# -_-__20241004.net
KiCad netlist of a schematic drawn in Altium Designer
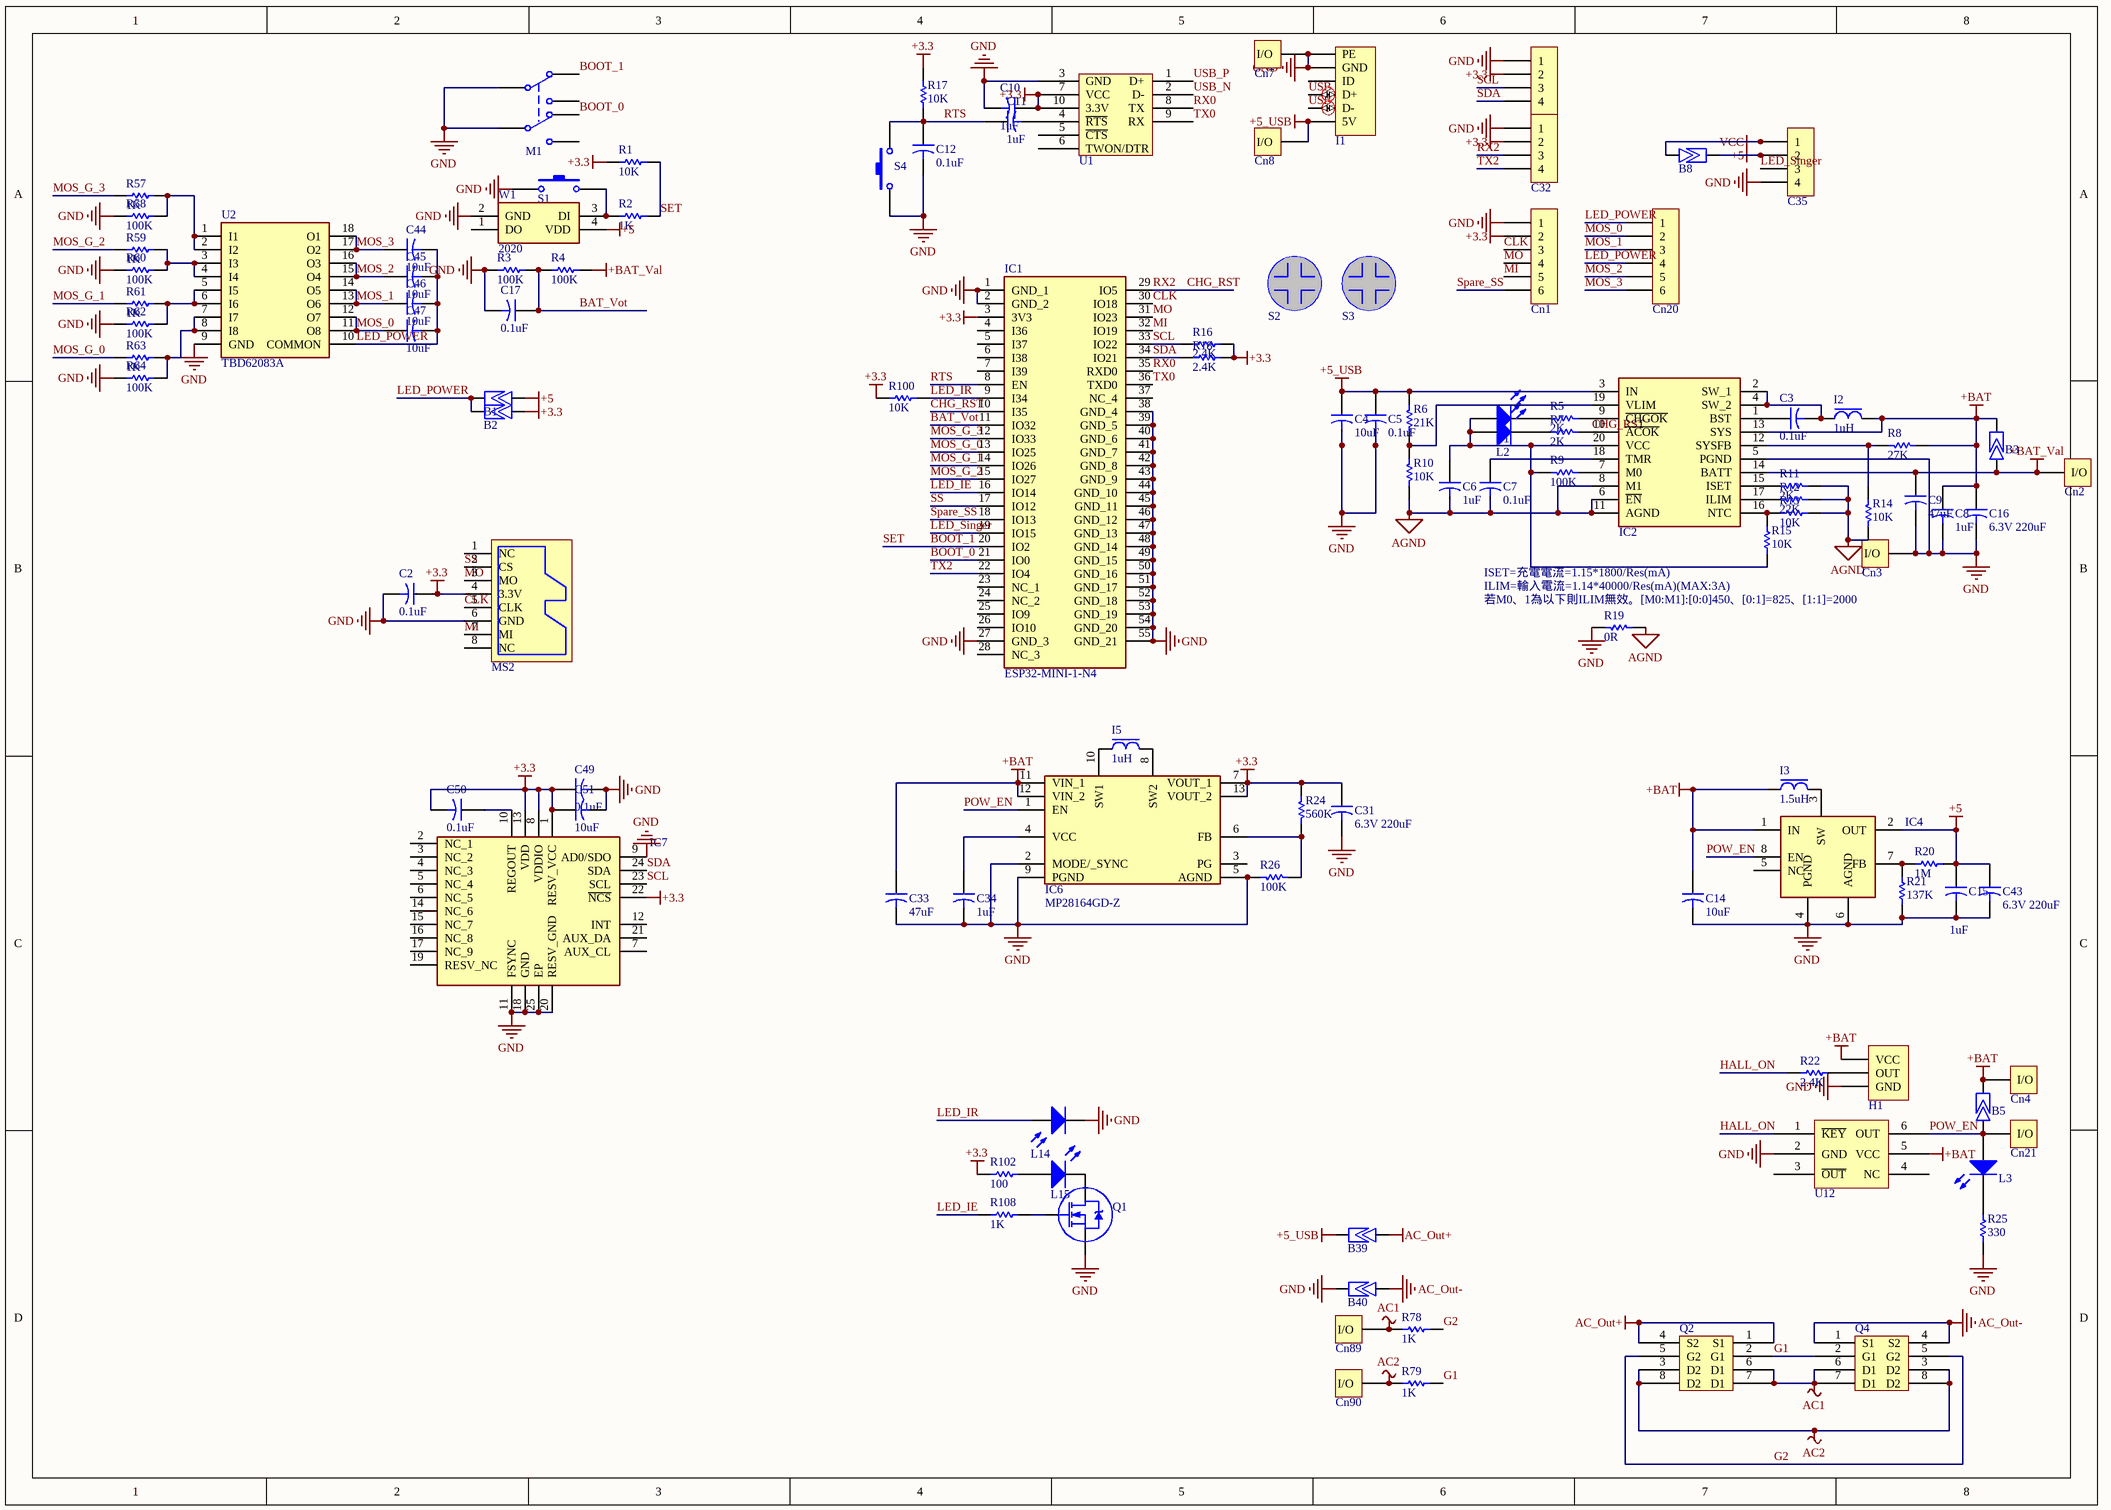
[diagram p0: 幻影光靈-學院-武器_20241004.SchDoc]

(export (version "E")
  (design (tool "Eeschema 10.0.6"))
  (components
    (comp (ref "B1")
      (value "不短路")
      (footprint "BYPASS-0805")
      (description "短路焊點(如標註短路則需額外補錫使其短路)")
      (libsource (lib "MyLibray") (part "Bypass"))
    )
    (comp (ref "B2")
      (value "短路")
      (footprint "BYPASS-0805")
      (description "短路焊點(如標註短路則需額外補錫使其短路)")
      (libsource (lib "MyLibray") (part "Bypass"))
    )
    (comp (ref "B3")
      (value "不短路")
      (footprint "BYPASS-0805")
      (description "短路焊點(如標註短路則需額外補錫使其短路)")
      (libsource (lib "MyLibray") (part "Bypass"))
    )
    (comp (ref "B5")
      (value "短路")
      (footprint "BYPASS-0402")
      (description "短路焊點(如標註短路則需額外補錫使其短路)")
      (libsource (lib "MyLibray") (part "Bypass"))
    )
    (comp (ref "B8")
      (value "短路")
      (footprint "BYPASS-0805")
      (description "短路焊點(如標註短路則需額外補錫使其短路)")
      (libsource (lib "MyLibray") (part "Bypass"))
    )
    (comp (ref "B39")
      (value "短路")
      (footprint "BYPASS-1206")
      (description "短路焊點(如標註短路則需額外補錫使其短路)")
      (libsource (lib "MyLibray") (part "Bypass"))
    )
    (comp (ref "B40")
      (value "短路")
      (footprint "BYPASS-1206")
      (description "短路焊點(如標註短路則需額外補錫使其短路)")
      (libsource (lib "MyLibray") (part "Bypass"))
    )
    (comp (ref "C1")
      (value "KF2510-4")
      (footprint "Connector_KF2510-4A")
      (description "接線端子")
      (libsource (lib "MyLibray") (part "Contact(4P)"))
    )
    (comp (ref "C2")
      (value "0.1uF")
      (footprint "Cap-0603")
      (description "電容")
      (libsource (lib "MyLibray") (part "Cap"))
    )
    (comp (ref "C3")
      (value "0.1uF")
      (footprint "Cap-0603")
      (description "電容")
      (libsource (lib "MyLibray") (part "Cap"))
    )
    (comp (ref "C4")
      (value "10uF")
      (footprint "Cap-0603")
      (description "電容")
      (libsource (lib "MyLibray") (part "Cap"))
    )
    (comp (ref "C5")
      (value "0.1uF")
      (footprint "Cap-0603")
      (description "電容")
      (libsource (lib "MyLibray") (part "Cap"))
    )
    (comp (ref "C6")
      (value "1uF")
      (footprint "Cap-0603")
      (description "電容")
      (libsource (lib "MyLibray") (part "Cap"))
    )
    (comp (ref "C7")
      (value "0.1uF")
      (footprint "Cap-0603")
      (description "電容")
      (libsource (lib "MyLibray") (part "Cap"))
    )
    (comp (ref "C8")
      (value "1uF")
      (footprint "Cap-0603")
      (description "電容")
      (libsource (lib "MyLibray") (part "Cap"))
    )
    (comp (ref "C9")
      (value "47uF")
      (footprint "CAP-1210")
      (description "電容")
      (libsource (lib "MyLibray") (part "Cap"))
    )
    (comp (ref "C10")
      (value "1uF")
      (footprint "Cap-0603")
      (description "電容")
      (libsource (lib "MyLibray") (part "Cap"))
    )
    (comp (ref "C11")
      (value "1uF")
      (footprint "Cap-0603")
      (description "電容")
      (libsource (lib "") (part "Cap_1"))
    )
    (comp (ref "C12")
      (value "0.1uF")
      (footprint "Cap-0603")
      (description "電容")
      (libsource (lib "") (part "Cap_1"))
    )
    (comp (ref "C14")
      (value "10uF")
      (footprint "Cap-0603")
      (description "電容")
      (libsource (lib "MyLibray") (part "Cap"))
    )
    (comp (ref "C15")
      (value "1uF")
      (footprint "Cap-0603")
      (description "電容")
      (libsource (lib "MyLibray") (part "Cap"))
    )
    (comp (ref "C16")
      (value "6.3V 220uF")
      (footprint "CAP-B3528")
      (description "電容")
      (libsource (lib "MyLibray") (part "Cap"))
    )
    (comp (ref "C17")
      (value "0.1uF")
      (footprint "Cap-0603")
      (description "電容")
      (libsource (lib "MyLibray") (part "Cap"))
    )
    (comp (ref "C31")
      (value "6.3V 220uF")
      (footprint "CAP-B3528")
      (description "電容")
      (libsource (lib "MyLibray") (part "Cap"))
    )
    (comp (ref "C32")
      (value "KF2510-4")
      (footprint "Connector_KF2510-4A")
      (description "接線端子")
      (libsource (lib "MyLibray") (part "Contact(4P)"))
    )
    (comp (ref "C33")
      (value "47uF")
      (footprint "Cap-0603")
      (description "電容")
      (libsource (lib "MyLibray") (part "Cap"))
    )
    (comp (ref "C34")
      (value "1uF")
      (footprint "Cap-0603")
      (description "電容")
      (libsource (lib "MyLibray") (part "Cap"))
    )
    (comp (ref "C35")
      (value "KF2510-4")
      (footprint "Connector_KF2510-4A")
      (description "接線端子")
      (libsource (lib "MyLibray") (part "Contact(4P)"))
    )
    (comp (ref "C43")
      (value "6.3V 220uF")
      (footprint "CAP-B3528")
      (description "電容")
      (libsource (lib "MyLibray") (part "Cap"))
    )
    (comp (ref "C44")
      (value "10uF")
      (footprint "Cap-0603")
      (description "電容")
      (libsource (lib "MyLibray") (part "Cap"))
    )
    (comp (ref "C45")
      (value "10uF")
      (footprint "Cap-0603")
      (description "電容")
      (libsource (lib "MyLibray") (part "Cap"))
    )
    (comp (ref "C46")
      (value "10uF")
      (footprint "Cap-0603")
      (description "電容")
      (libsource (lib "MyLibray") (part "Cap"))
    )
    (comp (ref "C47")
      (value "10uF")
      (footprint "Cap-0603")
      (description "電容")
      (libsource (lib "MyLibray") (part "Cap"))
    )
    (comp (ref "C49")
      (value "0.1uF")
      (footprint "Cap-0603")
      (description "電容")
      (libsource (lib "MyLibray") (part "Cap"))
    )
    (comp (ref "C50")
      (value "0.1uF")
      (footprint "Cap-0603")
      (description "電容")
      (libsource (lib "MyLibray") (part "Cap"))
    )
    (comp (ref "C51")
      (value "10uF")
      (footprint "Cap-0603")
      (description "電容")
      (libsource (lib "MyLibray") (part "Cap"))
    )
    (comp (ref "Cn1")
      (value "KF2510-6")
      (footprint "Connector_KF2510-6A")
      (description "接線端子")
      (libsource (lib "MyLibray") (part "Contact(6P)"))
    )
    (comp (ref "Cn2")
      (value "Contact")
      (footprint "Contact_Joints1*0.5")
      (description "接線端子、接點、郵票孔(非焊接元件)")
      (libsource (lib "") (part "Contact_2"))
    )
    (comp (ref "Cn3")
      (value "Contact")
      (footprint "Contact_Joints1*0.5")
      (description "接線端子、接點、郵票孔(非焊接元件)")
      (libsource (lib "") (part "Contact_1"))
    )
    (comp (ref "Cn4")
      (value "Contact")
      (footprint "Contact_Joints1*0.5")
      (description "接線端子、接點、郵票孔(非焊接元件)")
      (libsource (lib "") (part "Contact_2"))
    )
    (comp (ref "Cn7")
      (value "Contact")
      (footprint "Contact_Joints1*0.5")
      (description "接線端子、接點、郵票孔(非焊接元件)")
      (libsource (lib "") (part "Contact_1"))
    )
    (comp (ref "Cn8")
      (value "Contact")
      (footprint "Contact_Joints1*0.5")
      (description "接線端子、接點、郵票孔(非焊接元件)")
      (libsource (lib "") (part "Contact_1"))
    )
    (comp (ref "Cn20")
      (value "KF2510-6")
      (footprint "Connector_KF2510-6A")
      (description "接線端子")
      (libsource (lib "MyLibray") (part "Contact(6P)"))
    )
    (comp (ref "Cn21")
      (value "Contact")
      (footprint "Contact_Joints1*0.5")
      (description "接線端子、接點、郵票孔(非焊接元件)")
      (libsource (lib "") (part "Contact_2"))
    )
    (comp (ref "Cn89")
      (value "Contact")
      (footprint "Contact_Joints1*0.5")
      (description "接線端子、接點、郵票孔(非焊接元件)")
      (libsource (lib "MyLibray") (part "Contact"))
    )
    (comp (ref "Cn90")
      (value "Contact")
      (footprint "Contact_Joints1*0.5")
      (description "接線端子、接點、郵票孔(非焊接元件)")
      (libsource (lib "MyLibray") (part "Contact"))
    )
    (comp (ref "H1")
      (value "A3212#不用SMT")
      (footprint "SOT 23-3")
      (description "感測器_霍爾")
      (libsource (lib "MyLibray") (part "Sensor_Hall"))
    )
    (comp (ref "I1")
      (value "Interface_USB-Micro")
      (footprint "Interface_USB-micro")
      (description "接頭_USB-Micro")
      (libsource (lib "MyLibray") (part "Interface_USB-Micro"))
    )
    (comp (ref "I2")
      (value "1uH")
      (footprint "Inductor-0630")
      (description "電感")
      (libsource (lib "MyLibray") (part "Inductor"))
    )
    (comp (ref "I3")
      (value "1.5uH")
      (footprint "Inductor-0630")
      (description "電感")
      (libsource (lib "MyLibray") (part "Inductor"))
    )
    (comp (ref "I5")
      (value "1uH")
      (footprint "Inductor-0630")
      (description "一體成型電感")
      (libsource (lib "") (part "Inductor_1"))
    )
    (comp (ref "IC1")
      (value "ESP32-MINI-1-N4")
      (footprint "SamacSys:ESP32MINI1N4")
      (description "Integrated Circuit")
      (fields (field (name "MOUSER PART NUMBER") "356-ESP32-MINI1PH3Q0"))
      (libsource (lib "*") (part "ESP32-MINI-1-N4"))
    )
    (comp (ref "IC2")
      (value "MP2617BGL-P")
      (footprint "MP2617BGL")
      (fields (field (name "MOUSER PART NUMBER") "946-MP2617BGL-P"))
      (libsource (lib "MyLibray") (part "MP2617BGL-P"))
    )
    (comp (ref "IC4")
      (value "MP3414AGJ-Z")
      (footprint "SOT 23-8")
      (description "同步升压IC")
      (fields
        (field (name "MANUFACTURER_PART_NUMBER") "MP3414DJ-LF-Z")
        (field (name "MOUSER PART NUMBER") "946-MP3414DJLFZ")
      )
      (libsource (lib "MyLibray") (part "MP3414DJ-LF-Z"))
    )
    (comp (ref "IC6")
      (value "MP28164GD-Z")
      (footprint "MP28164GDZ")
      (description "升降壓IC 2.5~5.5 to 1.5~5")
      (fields (field (name "MOUSER PART NUMBER") "946-MP28164GD-Z"))
      (libsource (lib "MyLibray") (part "MP28164GD-Z"))
    )
    (comp (ref "IC7")
      (value "MPU-9250")
      (footprint "QFN-24")
      (description "I2C,SPI,9軸陀螺儀")
      (fields (field (name "MOUSER PART NUMBER") "410-MPU-9250"))
      (libsource (lib "MyLibray") (part "MPU-9250"))
    )
    (comp (ref "L1")
      (value "紅")
      (footprint "LED-0603")
      (description "LED")
      (libsource (lib "MyLibray") (part "LED"))
    )
    (comp (ref "L2")
      (value "綠")
      (footprint "LED-0603")
      (description "LED")
      (libsource (lib "MyLibray") (part "LED"))
    )
    (comp (ref "L3")
      (value "綠")
      (footprint "LED-0603")
      (description "LED")
      (libsource (lib "MyLibray") (part "LED"))
    )
    (comp (ref "L14")
      (value "LED-IR")
      (footprint "LED-IR-1206")
      (description "LED,紅外線接收")
      (libsource (lib "MyLibray") (part "LED-IR"))
    )
    (comp (ref "L15")
      (value "LED-IE")
      (footprint "LED-IE-1206")
      (description "LED,,紅外線發射")
      (libsource (lib "") (part "LED_1"))
    )
    (comp (ref "M1")
      (value "MST22D18G2")
      (footprint "Switch_MST22D18G2")
      (description "開關_滑動_2通道")
      (libsource (lib "MyLibray") (part "Switch_Slide_2"))
    )
    (comp (ref "MS2")
      (value "Interface_MicroSD card slot")
      (footprint "Interface_MicroSD card slot")
      (description "Micro SD 卡座")
      (libsource (lib "MyLibray") (part "Interface_MicroSD card slot"))
    )
    (comp (ref "Q1")
      (value "AO3400")
      (footprint "SOT 23-3")
      (description "場效電晶體_N")
      (libsource (lib "MyLibray") (part "MOS-N"))
    )
    (comp (ref "Q2")
      (value "MOS_Dual P_AON2801")
      (footprint "DFN-6_2x2")
      (description "MOS,雙PMOS")
      (libsource (lib "MyLibray") (part "MOS_Dual P_AON2801"))
    )
    (comp (ref "Q4")
      (value "MOS_Dual N_AON2800")
      (footprint "DFN-6_2x2")
      (description "MOS,雙NMOS")
      (libsource (lib "MyLibray") (part "MOS_Dual N_AON2800"))
    )
    (comp (ref "R1")
      (value "10K")
      (footprint "Res-0603")
      (description "電阻")
      (libsource (lib "MyLibray") (part "Res"))
    )
    (comp (ref "R2")
      (value "1K")
      (footprint "Res-0603")
      (description "電阻")
      (libsource (lib "MyLibray") (part "Res"))
    )
    (comp (ref "R3")
      (value "100K")
      (footprint "Res-0603")
      (description "電阻")
      (libsource (lib "MyLibray") (part "Res"))
    )
    (comp (ref "R4")
      (value "100K")
      (footprint "Res-0603")
      (description "電阻")
      (libsource (lib "MyLibray") (part "Res"))
    )
    (comp (ref "R5")
      (value "2K")
      (footprint "Res-0603")
      (description "電阻")
      (libsource (lib "MyLibray") (part "Res"))
    )
    (comp (ref "R6")
      (value "21K")
      (footprint "Res-0603")
      (description "電阻")
      (libsource (lib "MyLibray") (part "Res"))
    )
    (comp (ref "R7")
      (value "2K")
      (footprint "Res-0603")
      (description "電阻")
      (libsource (lib "MyLibray") (part "Res"))
    )
    (comp (ref "R8")
      (value "27K")
      (footprint "Res-0603")
      (description "電阻")
      (libsource (lib "MyLibray") (part "Res"))
    )
    (comp (ref "R9")
      (value "100K")
      (footprint "Res-0603")
      (description "電阻")
      (libsource (lib "MyLibray") (part "Res"))
    )
    (comp (ref "R10")
      (value "10K")
      (footprint "Res-0603")
      (description "電阻")
      (libsource (lib "MyLibray") (part "Res"))
    )
    (comp (ref "R11")
      (value "2K")
      (footprint "Res-0603")
      (description "電阻")
      (libsource (lib "MyLibray") (part "Res"))
    )
    (comp (ref "R12")
      (value "22K")
      (footprint "Res-0603")
      (description "電阻")
      (libsource (lib "MyLibray") (part "Res"))
    )
    (comp (ref "R13")
      (value "10K")
      (footprint "Res-0603")
      (description "電阻")
      (libsource (lib "MyLibray") (part "Res"))
    )
    (comp (ref "R14")
      (value "10K")
      (footprint "Res-0603")
      (description "電阻")
      (libsource (lib "MyLibray") (part "Res"))
    )
    (comp (ref "R15")
      (value "10K")
      (footprint "Res-0603")
      (description "電阻")
      (libsource (lib "MyLibray") (part "Res"))
    )
    (comp (ref "R16")
      (value "2.4K")
      (footprint "Res-0603")
      (description "電阻")
      (libsource (lib "MyLibray") (part "Res"))
    )
    (comp (ref "R17")
      (value "10K")
      (footprint "Res-0603")
      (description "電阻")
      (libsource (lib "MyLibray") (part "Res"))
    )
    (comp (ref "R18")
      (value "2.4K")
      (footprint "Res-0603")
      (description "電阻")
      (libsource (lib "MyLibray") (part "Res"))
    )
    (comp (ref "R19")
      (value "0R")
      (footprint "Res-0603")
      (description "電阻")
      (libsource (lib "MyLibray") (part "Res"))
    )
    (comp (ref "R20")
      (value "1M")
      (footprint "Res-0603")
      (description "電阻")
      (libsource (lib "MyLibray") (part "Res"))
    )
    (comp (ref "R21")
      (value "137K")
      (footprint "Res-0603")
      (description "電阻")
      (libsource (lib "MyLibray") (part "Res"))
    )
    (comp (ref "R22")
      (value "2.4K")
      (footprint "Res-0603")
      (description "電阻")
      (libsource (lib "MyLibray") (part "Res"))
    )
    (comp (ref "R24")
      (value "560K")
      (footprint "Res-0603")
      (description "電阻")
      (libsource (lib "MyLibray") (part "Res"))
    )
    (comp (ref "R25")
      (value "330")
      (footprint "Res-0603")
      (description "電阻")
      (libsource (lib "MyLibray") (part "Res"))
    )
    (comp (ref "R26")
      (value "100K")
      (footprint "Res-0603")
      (description "電阻")
      (libsource (lib "MyLibray") (part "Res"))
    )
    (comp (ref "R57")
      (value "1K")
      (footprint "Res-0603")
      (description "電阻")
      (libsource (lib "MyLibray") (part "Res"))
    )
    (comp (ref "R58")
      (value "100K")
      (footprint "Res-0603")
      (description "電阻")
      (libsource (lib "MyLibray") (part "Res"))
    )
    (comp (ref "R59")
      (value "1K")
      (footprint "Res-0603")
      (description "電阻")
      (libsource (lib "MyLibray") (part "Res"))
    )
    (comp (ref "R60")
      (value "100K")
      (footprint "Res-0603")
      (description "電阻")
      (libsource (lib "MyLibray") (part "Res"))
    )
    (comp (ref "R61")
      (value "1K")
      (footprint "Res-0603")
      (description "電阻")
      (libsource (lib "MyLibray") (part "Res"))
    )
    (comp (ref "R62")
      (value "100K")
      (footprint "Res-0603")
      (description "電阻")
      (libsource (lib "MyLibray") (part "Res"))
    )
    (comp (ref "R63")
      (value "1K")
      (footprint "Res-0603")
      (description "電阻")
      (libsource (lib "MyLibray") (part "Res"))
    )
    (comp (ref "R64")
      (value "100K")
      (footprint "Res-0603")
      (description "電阻")
      (libsource (lib "MyLibray") (part "Res"))
    )
    (comp (ref "R78")
      (value "1K")
      (footprint "Res-0603")
      (description "電阻")
      (libsource (lib "MyLibray") (part "Res"))
    )
    (comp (ref "R79")
      (value "1K")
      (footprint "Res-0603")
      (description "電阻")
      (libsource (lib "MyLibray") (part "Res"))
    )
    (comp (ref "R100")
      (value "10K")
      (footprint "Res-0603")
      (description "電阻")
      (libsource (lib "MyLibray") (part "Res"))
    )
    (comp (ref "R102")
      (value "100")
      (footprint "Res-0603")
      (description "電阻")
      (libsource (lib "MyLibray") (part "Res"))
    )
    (comp (ref "R108")
      (value "1K")
      (footprint "Res-0603")
      (description "電阻")
      (libsource (lib "MyLibray") (part "Res"))
    )
    (comp (ref "S1")
      (value "Switch")
      (footprint "Switch SMD-3.6*6*2.5")
      (description "開關_按鍵")
      (libsource (lib "MyLibray") (part "Switch"))
    )
    (comp (ref "S2")
      (value "M3")
      (footprint "Screw M3")
      (description "螺絲(非焊接元件)")
      (libsource (lib "MyLibray") (part "Screw"))
    )
    (comp (ref "S3")
      (value "M3")
      (footprint "Screw M3")
      (description "螺絲(非焊接元件)")
      (libsource (lib "MyLibray") (part "Screw"))
    )
    (comp (ref "S4")
      (value "Switch")
      (footprint "Switch SMD-3.6*6*2.5")
      (description "開關_按鍵")
      (libsource (lib "MyLibray") (part "Switch"))
    )
    (comp (ref "U1")
      (value "CH340X")
      (footprint "SSOP-10")
      (description "USB轉TTL芯片")
      (libsource (lib "MyLibray") (part "CH340X"))
    )
    (comp (ref "U2")
      (value "TBD62083A")
      (footprint "TSSOP-18")
      (description "閘極驅動器 P型 50V 0.5A")
      (fields
        (field (name "MOUSER PART NUMBER") "757-TBD60183AFNGEL")
        (field (name "MANUFACTURER_PART_NUMBER") "TBD62083AFNG,EL")
      )
      (libsource (lib "MyLibray") (part "TBD62083A"))
    )
    (comp (ref "U12")
      (value "CS2130#不用SMT")
      (footprint "SOT 23-6")
      (description "單鍵ON/OFF芯片")
      (libsource (lib "MyLibray") (part "CS2130"))
    )
    (comp (ref "W1")
      (value "2020")
      (footprint "LED-WS2812B-2020")
      (description "LED幻彩燈珠")
      (fields (field (name "MANUFACTURER_PART_NUMBER") "4684") (field (name "MOUSER PART NUMBER") "485-4684"))
      (libsource (lib "MyLibray") (part "WS2812B"))
    )
  )
  (nets
    (net (code "1") (name "+3.3") (class "Default")
      (node (ref "B2") (pin "2") (pinfunction "2_2") (pintype "passive"))
      (node (ref "C1") (pin "2") (pinfunction "2_2") (pintype "passive"))
      (node (ref "C10") (pin "1") (pinfunction "1_1") (pintype "passive"))
      (node (ref "C2") (pin "1") (pinfunction "1_1") (pintype "passive"))
      (node (ref "C31") (pin "1") (pinfunction "1_1") (pintype "passive"))
      (node (ref "C32") (pin "2") (pinfunction "2_2") (pintype "passive"))
      (node (ref "C49") (pin "1") (pinfunction "1_1") (pintype "passive"))
      (node (ref "C50") (pin "2") (pinfunction "2_2") (pintype "passive"))
      (node (ref "C51") (pin "1") (pinfunction "1_1") (pintype "passive"))
      (node (ref "Cn1") (pin "2") (pinfunction "2_2") (pintype "passive"))
      (node (ref "IC1") (pin "3") (pinfunction "3V3_3") (pintype "passive"))
      (node (ref "IC6") (pin "13") (pinfunction "VOUT_2_13") (pintype "passive"))
      (node (ref "IC6") (pin "7") (pinfunction "VOUT_1_7") (pintype "passive"))
      (node (ref "IC7") (pin "1") (pinfunction "RESV_VCC_1") (pintype "passive"))
      (node (ref "IC7") (pin "13") (pinfunction "VDD_13") (pintype "passive"))
      (node (ref "IC7") (pin "22") (pinfunction "~{NCS}_22") (pintype "passive"))
      (node (ref "IC7") (pin "8") (pinfunction "VDDIO_8") (pintype "passive"))
      (node (ref "MS2") (pin "4") (pinfunction "3.3V_4") (pintype "power_in"))
      (node (ref "R1") (pin "1") (pinfunction "1_1") (pintype "passive"))
      (node (ref "R100") (pin "1") (pinfunction "1_1") (pintype "passive"))
      (node (ref "R102") (pin "1") (pinfunction "1_1") (pintype "passive"))
      (node (ref "R16") (pin "1") (pinfunction "1_1") (pintype "passive"))
      (node (ref "R17") (pin "1") (pinfunction "1_1") (pintype "passive"))
      (node (ref "R18") (pin "2") (pinfunction "2_2") (pintype "passive"))
      (node (ref "R24") (pin "2") (pinfunction "2_2") (pintype "passive"))
      (node (ref "U1") (pin "10") (pinfunction "3.3V_10") (pintype "passive"))
      (node (ref "U1") (pin "7") (pinfunction "VCC_7") (pintype "passive"))
    )
    (net (code "2") (name "+5") (class "Default")
      (node (ref "B1") (pin "2") (pinfunction "2_2") (pintype "passive"))
      (node (ref "B8") (pin "1") (pinfunction "1_1") (pintype "passive"))
      (node (ref "C15") (pin "1") (pinfunction "1_1") (pintype "passive"))
      (node (ref "C35") (pin "2") (pinfunction "2_2") (pintype "passive"))
      (node (ref "C43") (pin "1") (pinfunction "1_1") (pintype "passive"))
      (node (ref "IC4") (pin "2") (pinfunction "OUT_2") (pintype "passive"))
      (node (ref "R20") (pin "1") (pinfunction "1_1") (pintype "passive"))
      (node (ref "W1") (pin "4") (pinfunction "VDD_4") (pintype "passive"))
    )
    (net (code "3") (name "+5_USB") (class "Default")
      (node (ref "B39") (pin "1") (pinfunction "1_1") (pintype "passive"))
      (node (ref "C4") (pin "1") (pinfunction "1_1") (pintype "passive"))
      (node (ref "C5") (pin "1") (pinfunction "1_1") (pintype "passive"))
      (node (ref "Cn8") (pin "1") (pinfunction "I/O_1") (pintype "passive"))
      (node (ref "I1") (pin "1") (pinfunction "5V_1") (pintype "passive"))
      (node (ref "IC2") (pin "3") (pinfunction "IN_3") (pintype "passive"))
      (node (ref "R6") (pin "1") (pinfunction "1_1") (pintype "passive"))
    )
    (net (code "4") (name "+BAT") (class "Default")
      (node (ref "B3") (pin "1") (pinfunction "1_1") (pintype "passive"))
      (node (ref "B5") (pin "1") (pinfunction "1_1") (pintype "passive"))
      (node (ref "C14") (pin "1") (pinfunction "1_1") (pintype "passive"))
      (node (ref "C16") (pin "1") (pinfunction "1_1") (pintype "passive"))
      (node (ref "C33") (pin "1") (pinfunction "1_1") (pintype "passive"))
      (node (ref "C8") (pin "1") (pinfunction "1_1") (pintype "passive"))
      (node (ref "Cn4") (pin "1") (pinfunction "I/O_1") (pintype "passive"))
      (node (ref "H1") (pin "1") (pinfunction "VCC_1") (pintype "power_in"))
      (node (ref "I2") (pin "2") (pinfunction "2_2") (pintype "passive"))
      (node (ref "I3") (pin "1") (pinfunction "1_1") (pintype "passive"))
      (node (ref "IC2") (pin "13") (pinfunction "SYS_13") (pintype "passive"))
      (node (ref "IC4") (pin "1") (pinfunction "IN_1") (pintype "passive"))
      (node (ref "IC6") (pin "11") (pinfunction "VIN_1_11") (pintype "passive"))
      (node (ref "IC6") (pin "12") (pinfunction "VIN_2_12") (pintype "passive"))
      (node (ref "R8") (pin "2") (pinfunction "2_2") (pintype "passive"))
      (node (ref "U12") (pin "5") (pinfunction "VCC_5") (pintype "passive"))
    )
    (net (code "5") (name "+BAT_Val") (class "Default")
      (node (ref "B3") (pin "2") (pinfunction "2_2") (pintype "passive"))
      (node (ref "C9") (pin "1") (pinfunction "1_1") (pintype "passive"))
      (node (ref "Cn2") (pin "1") (pinfunction "I/O_1") (pintype "passive"))
      (node (ref "IC2") (pin "14") (pinfunction "BATT_14") (pintype "passive"))
      (node (ref "R4") (pin "2") (pinfunction "2_2") (pintype "passive"))
    )
    (net (code "6") (name "/BAT_Vot") (class "Default")
      (node (ref "C17") (pin "1") (pinfunction "1_1") (pintype "passive"))
      (node (ref "IC1") (pin "11") (pinfunction "IO32_11") (pintype "passive"))
      (node (ref "R3") (pin "2") (pinfunction "2_2") (pintype "passive"))
      (node (ref "R4") (pin "1") (pinfunction "1_1") (pintype "passive"))
    )
    (net (code "7") (name "/BOOT_0") (class "Default")
      (node (ref "IC1") (pin "21") (pinfunction "IO0_21") (pintype "passive"))
      (node (ref "M1") (pin "5") (pinfunction "5_5") (pintype "passive"))
    )
    (net (code "8") (name "/BOOT_1") (class "Default")
      (node (ref "IC1") (pin "20") (pinfunction "IO2_20") (pintype "passive"))
      (node (ref "M1") (pin "2") (pinfunction "2_2") (pintype "passive"))
      (node (ref "R1") (pin "2") (pinfunction "2_2") (pintype "passive"))
      (node (ref "R2") (pin "2") (pinfunction "2_2") (pintype "passive"))
    )
    (net (code "9") (name "/CHG_RST") (class "Default")
      (node (ref "C32") (pin "3") (pinfunction "3_3") (pintype "passive"))
      (node (ref "IC1") (pin "10") (pinfunction "I35_10") (pintype "passive"))
      (node (ref "IC1") (pin "29") (pinfunction "IO5_29") (pintype "passive"))
      (node (ref "IC2") (pin "10") (pinfunction "~{ACOK}_10") (pintype "passive"))
      (node (ref "R7") (pin "2") (pinfunction "2_2") (pintype "passive"))
    )
    (net (code "10") (name "/CLK") (class "Default")
      (node (ref "Cn1") (pin "3") (pinfunction "3_3") (pintype "passive"))
      (node (ref "IC1") (pin "30") (pinfunction "IO18_30") (pintype "passive"))
      (node (ref "MS2") (pin "5") (pinfunction "CLK_5") (pintype "passive"))
    )
    (net (code "11") (name "/G1") (class "Default")
      (node (ref "Q2") (pin "2") (pinfunction "G1_2") (pintype "passive"))
      (node (ref "Q4") (pin "2") (pinfunction "G1_2") (pintype "passive"))
      (node (ref "R79") (pin "1") (pinfunction "1_1") (pintype "passive"))
    )
    (net (code "12") (name "/G2") (class "Default")
      (node (ref "Q2") (pin "5") (pinfunction "G2_5") (pintype "passive"))
      (node (ref "Q4") (pin "5") (pinfunction "G2_5") (pintype "passive"))
      (node (ref "R78") (pin "1") (pinfunction "1_1") (pintype "passive"))
    )
    (net (code "13") (name "/HALL_ON") (class "Default")
      (node (ref "R22") (pin "1") (pinfunction "1_1") (pintype "passive"))
      (node (ref "U12") (pin "1") (pinfunction "~{KEY}_1") (pintype "passive"))
    )
    (net (code "14") (name "/LED_IE") (class "Default")
      (node (ref "IC1") (pin "16") (pinfunction "IO14_16") (pintype "passive"))
      (node (ref "R108") (pin "1") (pinfunction "1_1") (pintype "passive"))
    )
    (net (code "15") (name "/LED_IR") (class "Default")
      (node (ref "IC1") (pin "9") (pinfunction "I34_9") (pintype "passive"))
      (node (ref "L14") (pin "1") (pinfunction "A_1") (pintype "passive"))
      (node (ref "R100") (pin "2") (pinfunction "2_2") (pintype "passive"))
    )
    (net (code "16") (name "/LED_POWER") (class "Default")
      (node (ref "B1") (pin "1") (pinfunction "1_1") (pintype "passive"))
      (node (ref "B2") (pin "1") (pinfunction "1_1") (pintype "passive"))
      (node (ref "C44") (pin "2") (pinfunction "2_2") (pintype "passive"))
      (node (ref "C45") (pin "2") (pinfunction "2_2") (pintype "passive"))
      (node (ref "C46") (pin "2") (pinfunction "2_2") (pintype "passive"))
      (node (ref "C47") (pin "2") (pinfunction "2_2") (pintype "passive"))
      (node (ref "Cn20") (pin "1") (pinfunction "1_1") (pintype "passive"))
      (node (ref "Cn20") (pin "4") (pinfunction "4_4") (pintype "passive"))
      (node (ref "U2") (pin "10") (pinfunction "COMMON_10") (pintype "passive"))
    )
    (net (code "17") (name "/LED_Singer") (class "Default")
      (node (ref "C35") (pin "3") (pinfunction "3_3") (pintype "passive"))
      (node (ref "IC1") (pin "19") (pinfunction "IO15_19") (pintype "passive"))
    )
    (net (code "18") (name "/MI") (class "Default")
      (node (ref "Cn1") (pin "5") (pinfunction "5_5") (pintype "passive"))
      (node (ref "IC1") (pin "32") (pinfunction "IO19_32") (pintype "passive"))
      (node (ref "MS2") (pin "7") (pinfunction "MI_7") (pintype "passive"))
    )
    (net (code "19") (name "/MO") (class "Default")
      (node (ref "Cn1") (pin "4") (pinfunction "4_4") (pintype "passive"))
      (node (ref "IC1") (pin "31") (pinfunction "IO23_31") (pintype "passive"))
      (node (ref "MS2") (pin "3") (pinfunction "MO_3") (pintype "passive"))
    )
    (net (code "20") (name "/MOS_0") (class "Default")
      (node (ref "C47") (pin "1") (pinfunction "1_1") (pintype "passive"))
      (node (ref "Cn20") (pin "2") (pinfunction "2_2") (pintype "passive"))
      (node (ref "U2") (pin "11") (pinfunction "O8_11") (pintype "passive"))
      (node (ref "U2") (pin "12") (pinfunction "O7_12") (pintype "passive"))
    )
    (net (code "21") (name "/MOS_1") (class "Default")
      (node (ref "C46") (pin "1") (pinfunction "1_1") (pintype "passive"))
      (node (ref "Cn20") (pin "3") (pinfunction "3_3") (pintype "passive"))
      (node (ref "U2") (pin "13") (pinfunction "O6_13") (pintype "passive"))
      (node (ref "U2") (pin "14") (pinfunction "O5_14") (pintype "passive"))
    )
    (net (code "22") (name "/MOS_2") (class "Default")
      (node (ref "C45") (pin "1") (pinfunction "1_1") (pintype "passive"))
      (node (ref "Cn20") (pin "5") (pinfunction "5_5") (pintype "passive"))
      (node (ref "U2") (pin "15") (pinfunction "O4_15") (pintype "passive"))
      (node (ref "U2") (pin "16") (pinfunction "O3_16") (pintype "passive"))
    )
    (net (code "23") (name "/MOS_3") (class "Default")
      (node (ref "C44") (pin "1") (pinfunction "1_1") (pintype "passive"))
      (node (ref "Cn20") (pin "6") (pinfunction "6_6") (pintype "passive"))
      (node (ref "U2") (pin "17") (pinfunction "O2_17") (pintype "passive"))
      (node (ref "U2") (pin "18") (pinfunction "O1_18") (pintype "passive"))
    )
    (net (code "24") (name "/MOS_G_0") (class "Default")
      (node (ref "IC1") (pin "13") (pinfunction "IO25_13") (pintype "passive"))
      (node (ref "R63") (pin "1") (pinfunction "1_1") (pintype "passive"))
    )
    (net (code "25") (name "/MOS_G_1") (class "Default")
      (node (ref "IC1") (pin "14") (pinfunction "IO26_14") (pintype "passive"))
      (node (ref "R61") (pin "1") (pinfunction "1_1") (pintype "passive"))
    )
    (net (code "26") (name "/MOS_G_2") (class "Default")
      (node (ref "IC1") (pin "15") (pinfunction "IO27_15") (pintype "passive"))
      (node (ref "R59") (pin "1") (pinfunction "1_1") (pintype "passive"))
    )
    (net (code "27") (name "/MOS_G_3") (class "Default")
      (node (ref "IC1") (pin "12") (pinfunction "IO33_12") (pintype "passive"))
      (node (ref "R57") (pin "1") (pinfunction "1_1") (pintype "passive"))
    )
    (net (code "28") (name "/POW_EN") (class "Default")
      (node (ref "B5") (pin "2") (pinfunction "2_2") (pintype "passive"))
      (node (ref "Cn21") (pin "1") (pinfunction "I/O_1") (pintype "passive"))
      (node (ref "IC4") (pin "8") (pinfunction "EN_8") (pintype "passive"))
      (node (ref "IC6") (pin "1") (pinfunction "EN_1") (pintype "passive"))
      (node (ref "L3") (pin "2") (pinfunction "A_2") (pintype "passive"))
      (node (ref "U12") (pin "6") (pinfunction "OUT_6") (pintype "passive"))
    )
    (net (code "29") (name "/RTS") (class "Default")
      (node (ref "C11") (pin "1") (pinfunction "1_1") (pintype "passive"))
      (node (ref "C12") (pin "1") (pinfunction "1_1") (pintype "passive"))
      (node (ref "IC1") (pin "8") (pinfunction "EN_8") (pintype "passive"))
      (node (ref "R17") (pin "2") (pinfunction "2_2") (pintype "passive"))
      (node (ref "S4") (pin "1") (pinfunction "1_1") (pintype "passive"))
    )
    (net (code "30") (name "/RX0") (class "Default")
      (node (ref "IC1") (pin "35") (pinfunction "RXD0_35") (pintype "passive"))
      (node (ref "U1") (pin "8") (pinfunction "TX_8") (pintype "passive"))
    )
    (net (code "31") (name "/SCL") (class "Default")
      (node (ref "C1") (pin "3") (pinfunction "3_3") (pintype "passive"))
      (node (ref "IC1") (pin "33") (pinfunction "IO22_33") (pintype "passive"))
      (node (ref "IC7") (pin "23") (pinfunction "SCL_23") (pintype "passive"))
      (node (ref "R16") (pin "2") (pinfunction "2_2") (pintype "passive"))
    )
    (net (code "32") (name "/SDA") (class "Default")
      (node (ref "C1") (pin "4") (pinfunction "4_4") (pintype "passive"))
      (node (ref "IC1") (pin "34") (pinfunction "IO21_34") (pintype "passive"))
      (node (ref "IC7") (pin "24") (pinfunction "SDA_24") (pintype "passive"))
      (node (ref "R18") (pin "1") (pinfunction "1_1") (pintype "passive"))
    )
    (net (code "33") (name "/SS") (class "Default")
      (node (ref "IC1") (pin "17") (pinfunction "IO12_17") (pintype "passive"))
      (node (ref "MS2") (pin "2") (pinfunction "CS_2") (pintype "passive"))
    )
    (net (code "34") (name "/Spare_SS") (class "Default")
      (node (ref "Cn1") (pin "6") (pinfunction "6_6") (pintype "passive"))
      (node (ref "IC1") (pin "18") (pinfunction "IO13_18") (pintype "passive"))
    )
    (net (code "35") (name "/TX0") (class "Default")
      (node (ref "IC1") (pin "36") (pinfunction "TXD0_36") (pintype "passive"))
      (node (ref "U1") (pin "9") (pinfunction "RX_9") (pintype "passive"))
    )
    (net (code "36") (name "/TX2") (class "Default")
      (node (ref "C32") (pin "4") (pinfunction "4_4") (pintype "passive"))
      (node (ref "IC1") (pin "22") (pinfunction "IO4_22") (pintype "passive"))
    )
    (net (code "37") (name "/USB_N") (class "Default")
      (node (ref "I1") (pin "2") (pinfunction "D-_2") (pintype "bidirectional"))
      (node (ref "U1") (pin "2") (pinfunction "D-_2") (pintype "passive"))
    )
    (net (code "38") (name "/USB_P") (class "Default")
      (node (ref "I1") (pin "3") (pinfunction "D+_3") (pintype "bidirectional"))
      (node (ref "U1") (pin "1") (pinfunction "D+_1") (pintype "passive"))
    )
    (net (code "39") (name "AC1") (class "Default")
      (node (ref "Cn89") (pin "1") (pinfunction "I/O_1") (pintype "passive"))
      (node (ref "Q2") (pin "6") (pinfunction "D1_6") (pintype "passive"))
      (node (ref "Q2") (pin "7") (pinfunction "D1_7") (pintype "passive"))
      (node (ref "Q4") (pin "6") (pinfunction "D1_6") (pintype "passive"))
      (node (ref "Q4") (pin "7") (pinfunction "D1_7") (pintype "passive"))
      (node (ref "R78") (pin "2") (pinfunction "2_2") (pintype "passive"))
    )
    (net (code "40") (name "AC2") (class "Default")
      (node (ref "Cn90") (pin "1") (pinfunction "I/O_1") (pintype "passive"))
      (node (ref "Q2") (pin "3") (pinfunction "D2_3") (pintype "passive"))
      (node (ref "Q2") (pin "8") (pinfunction "D2_8") (pintype "passive"))
      (node (ref "Q4") (pin "3") (pinfunction "D2_3") (pintype "passive"))
      (node (ref "Q4") (pin "8") (pinfunction "D2_8") (pintype "passive"))
      (node (ref "R79") (pin "2") (pinfunction "2_2") (pintype "passive"))
    )
    (net (code "41") (name "AC_Out+") (class "Default")
      (node (ref "B39") (pin "2") (pinfunction "2_2") (pintype "passive"))
      (node (ref "Q2") (pin "1") (pinfunction "S1_1") (pintype "passive"))
      (node (ref "Q2") (pin "4") (pinfunction "S2_4") (pintype "passive"))
    )
    (net (code "42") (name "AC_Out-") (class "Default")
      (node (ref "B40") (pin "2") (pinfunction "2_2") (pintype "passive"))
      (node (ref "Q4") (pin "1") (pinfunction "S1_1") (pintype "passive"))
      (node (ref "Q4") (pin "4") (pinfunction "S2_4") (pintype "passive"))
    )
    (net (code "43") (name "AGND") (class "Default")
      (node (ref "C6") (pin "2") (pinfunction "2_2") (pintype "passive"))
      (node (ref "C7") (pin "2") (pinfunction "2_2") (pintype "passive"))
      (node (ref "IC2") (pin "11") (pinfunction "AGND_11") (pintype "passive"))
      (node (ref "IC2") (pin "6") (pinfunction "~{EN}_6") (pintype "passive"))
      (node (ref "IC2") (pin "8") (pinfunction "M1_8") (pintype "passive"))
      (node (ref "R10") (pin "2") (pinfunction "2_2") (pintype "passive"))
      (node (ref "R11") (pin "2") (pinfunction "2_2") (pintype "passive"))
      (node (ref "R12") (pin "2") (pinfunction "2_2") (pintype "passive"))
      (node (ref "R13") (pin "2") (pinfunction "2_2") (pintype "passive"))
      (node (ref "R14") (pin "2") (pinfunction "2_2") (pintype "passive"))
      (node (ref "R19") (pin "2") (pinfunction "2_2") (pintype "passive"))
    )
    (net (code "44") (name "GND") (class "Default")
      (node (ref "B40") (pin "1") (pinfunction "1_1") (pintype "passive"))
      (node (ref "C1") (pin "1") (pinfunction "1_1") (pintype "passive"))
      (node (ref "C10") (pin "2") (pinfunction "2_2") (pintype "passive"))
      (node (ref "C12") (pin "2") (pinfunction "2_2") (pintype "passive"))
      (node (ref "C14") (pin "2") (pinfunction "2_2") (pintype "passive"))
      (node (ref "C15") (pin "2") (pinfunction "2_2") (pintype "passive"))
      (node (ref "C16") (pin "2") (pinfunction "2_2") (pintype "passive"))
      (node (ref "C17") (pin "2") (pinfunction "2_2") (pintype "passive"))
      (node (ref "C2") (pin "2") (pinfunction "2_2") (pintype "passive"))
      (node (ref "C31") (pin "2") (pinfunction "2_2") (pintype "passive"))
      (node (ref "C32") (pin "1") (pinfunction "1_1") (pintype "passive"))
      (node (ref "C33") (pin "2") (pinfunction "2_2") (pintype "passive"))
      (node (ref "C34") (pin "2") (pinfunction "2_2") (pintype "passive"))
      (node (ref "C35") (pin "4") (pinfunction "4_4") (pintype "passive"))
      (node (ref "C4") (pin "2") (pinfunction "2_2") (pintype "passive"))
      (node (ref "C43") (pin "2") (pinfunction "2_2") (pintype "passive"))
      (node (ref "C49") (pin "2") (pinfunction "2_2") (pintype "passive"))
      (node (ref "C5") (pin "2") (pinfunction "2_2") (pintype "passive"))
      (node (ref "C51") (pin "2") (pinfunction "2_2") (pintype "passive"))
      (node (ref "C8") (pin "2") (pinfunction "2_2") (pintype "passive"))
      (node (ref "C9") (pin "2") (pinfunction "2_2") (pintype "passive"))
      (node (ref "Cn1") (pin "1") (pinfunction "1_1") (pintype "passive"))
      (node (ref "Cn3") (pin "1") (pinfunction "I/O_1") (pintype "passive"))
      (node (ref "Cn7") (pin "1") (pinfunction "I/O_1") (pintype "passive"))
      (node (ref "H1") (pin "3") (pinfunction "GND_3") (pintype "power_in"))
      (node (ref "I1") (pin "5") (pinfunction "GND_5") (pintype "passive"))
      (node (ref "I1") (pin "PE") (pinfunction "PE_PE") (pintype "passive"))
      (node (ref "IC1") (pin "1") (pinfunction "GND_1_1") (pintype "passive"))
      (node (ref "IC1") (pin "2") (pinfunction "GND_2_2") (pintype "passive"))
      (node (ref "IC1") (pin "27") (pinfunction "GND_3_27") (pintype "passive"))
      (node (ref "IC1") (pin "38") (pinfunction "GND_4_38") (pintype "passive"))
      (node (ref "IC1") (pin "39") (pinfunction "GND_5_39") (pintype "passive"))
      (node (ref "IC1") (pin "40") (pinfunction "GND_6_40") (pintype "passive"))
      (node (ref "IC1") (pin "41") (pinfunction "GND_7_41") (pintype "passive"))
      (node (ref "IC1") (pin "42") (pinfunction "GND_8_42") (pintype "passive"))
      (node (ref "IC1") (pin "43") (pinfunction "GND_9_43") (pintype "passive"))
      (node (ref "IC1") (pin "44") (pinfunction "GND_10_44") (pintype "passive"))
      (node (ref "IC1") (pin "45") (pinfunction "GND_11_45") (pintype "passive"))
      (node (ref "IC1") (pin "46") (pinfunction "GND_12_46") (pintype "passive"))
      (node (ref "IC1") (pin "47") (pinfunction "GND_13_47") (pintype "passive"))
      (node (ref "IC1") (pin "48") (pinfunction "GND_14_48") (pintype "passive"))
      (node (ref "IC1") (pin "49") (pinfunction "GND_15_49") (pintype "passive"))
      (node (ref "IC1") (pin "50") (pinfunction "GND_16_50") (pintype "passive"))
      (node (ref "IC1") (pin "51") (pinfunction "GND_17_51") (pintype "passive"))
      (node (ref "IC1") (pin "52") (pinfunction "GND_18_52") (pintype "passive"))
      (node (ref "IC1") (pin "53") (pinfunction "GND_19_53") (pintype "passive"))
      (node (ref "IC1") (pin "54") (pinfunction "GND_20_54") (pintype "passive"))
      (node (ref "IC1") (pin "55") (pinfunction "GND_21_55") (pintype "passive"))
      (node (ref "IC2") (pin "5") (pinfunction "PGND_5") (pintype "passive"))
      (node (ref "IC4") (pin "4") (pinfunction "PGND_4") (pintype "passive"))
      (node (ref "IC4") (pin "6") (pinfunction "AGND_6") (pintype "passive"))
      (node (ref "IC6") (pin "2") (pinfunction "MODE/_SYNC_2") (pintype "passive"))
      (node (ref "IC6") (pin "5") (pinfunction "AGND_5") (pintype "passive"))
      (node (ref "IC6") (pin "9") (pinfunction "PGND_9") (pintype "passive"))
      (node (ref "IC7") (pin "11") (pinfunction "FSYNC_11") (pintype "passive"))
      (node (ref "IC7") (pin "18") (pinfunction "GND_18") (pintype "passive"))
      (node (ref "IC7") (pin "20") (pinfunction "RESV_GND_20") (pintype "passive"))
      (node (ref "IC7") (pin "25") (pinfunction "EP_25") (pintype "passive"))
      (node (ref "IC7") (pin "9") (pinfunction "AD0/SDO_9") (pintype "passive"))
      (node (ref "L14") (pin "2") (pinfunction "K_2") (pintype "passive"))
      (node (ref "M1") (pin "1") (pinfunction "1_1") (pintype "passive"))
      (node (ref "M1") (pin "4") (pinfunction "4_4") (pintype "passive"))
      (node (ref "MS2") (pin "6") (pinfunction "GND_6") (pintype "power_in"))
      (node (ref "Q1") (pin "2") (pinfunction "S_2") (pintype "passive"))
      (node (ref "R19") (pin "1") (pinfunction "1_1") (pintype "passive"))
      (node (ref "R21") (pin "1") (pinfunction "1_1") (pintype "passive"))
      (node (ref "R25") (pin "1") (pinfunction "1_1") (pintype "passive"))
      (node (ref "R26") (pin "1") (pinfunction "1_1") (pintype "passive"))
      (node (ref "R3") (pin "1") (pinfunction "1_1") (pintype "passive"))
      (node (ref "R58") (pin "1") (pinfunction "1_1") (pintype "passive"))
      (node (ref "R60") (pin "1") (pinfunction "1_1") (pintype "passive"))
      (node (ref "R62") (pin "1") (pinfunction "1_1") (pintype "passive"))
      (node (ref "R64") (pin "1") (pinfunction "1_1") (pintype "passive"))
      (node (ref "S1") (pin "1") (pinfunction "1_1") (pintype "passive"))
      (node (ref "S4") (pin "2") (pinfunction "2_2") (pintype "passive"))
      (node (ref "U1") (pin "3") (pinfunction "GND_3") (pintype "passive"))
      (node (ref "U12") (pin "2") (pinfunction "GND_2") (pintype "passive"))
      (node (ref "U2") (pin "9") (pinfunction "GND_9") (pintype "passive"))
      (node (ref "W1") (pin "2") (pinfunction "GND_2") (pintype "passive"))
    )
    (net (code "45") (name "Net-(H1-OUT)") (class "Default")
      (node (ref "H1") (pin "2") (pinfunction "OUT_2") (pintype "power_in"))
      (node (ref "R22") (pin "2") (pinfunction "2_2") (pintype "passive"))
    )
    (net (code "46") (name "Net-(IC2-BST)") (class "Default")
      (node (ref "C3") (pin "1") (pinfunction "1_1") (pintype "passive"))
      (node (ref "IC2") (pin "1") (pinfunction "BST_1") (pintype "passive"))
    )
    (net (code "47") (name "Net-(IC2-ILIM)") (class "Default")
      (node (ref "IC2") (pin "17") (pinfunction "ILIM_17") (pintype "passive"))
      (node (ref "R12") (pin "1") (pinfunction "1_1") (pintype "passive"))
    )
    (net (code "48") (name "Net-(IC2-ISET)") (class "Default")
      (node (ref "IC2") (pin "15") (pinfunction "ISET_15") (pintype "passive"))
      (node (ref "R11") (pin "1") (pinfunction "1_1") (pintype "passive"))
    )
    (net (code "49") (name "Net-(IC2-M0)") (class "Default")
      (node (ref "IC2") (pin "7") (pinfunction "M0_7") (pintype "passive"))
      (node (ref "R9") (pin "2") (pinfunction "2_2") (pintype "passive"))
    )
    (net (code "50") (name "Net-(IC2-NTC)") (class "Default")
      (node (ref "IC2") (pin "16") (pinfunction "NTC_16") (pintype "passive"))
      (node (ref "R13") (pin "1") (pinfunction "1_1") (pintype "passive"))
      (node (ref "R15") (pin "2") (pinfunction "2_2") (pintype "passive"))
    )
    (net (code "51") (name "Net-(IC2-SW_1)") (class "Default")
      (node (ref "C3") (pin "2") (pinfunction "2_2") (pintype "passive"))
      (node (ref "I2") (pin "1") (pinfunction "1_1") (pintype "passive"))
      (node (ref "IC2") (pin "2") (pinfunction "SW_1_2") (pintype "passive"))
      (node (ref "IC2") (pin "4") (pinfunction "SW_2_4") (pintype "passive"))
    )
    (net (code "52") (name "Net-(IC2-SYSFB)") (class "Default")
      (node (ref "IC2") (pin "12") (pinfunction "SYSFB_12") (pintype "passive"))
      (node (ref "R14") (pin "1") (pinfunction "1_1") (pintype "passive"))
      (node (ref "R8") (pin "1") (pinfunction "1_1") (pintype "passive"))
    )
    (net (code "53") (name "Net-(IC2-TMR)") (class "Default")
      (node (ref "C7") (pin "1") (pinfunction "1_1") (pintype "passive"))
      (node (ref "IC2") (pin "18") (pinfunction "TMR_18") (pintype "passive"))
    )
    (net (code "54") (name "Net-(IC2-VCC)") (class "Default")
      (node (ref "C6") (pin "1") (pinfunction "1_1") (pintype "passive"))
      (node (ref "IC2") (pin "20") (pinfunction "VCC_20") (pintype "passive"))
      (node (ref "L1") (pin "2") (pinfunction "A_2") (pintype "passive"))
      (node (ref "L2") (pin "2") (pinfunction "A_2") (pintype "passive"))
      (node (ref "R15") (pin "1") (pinfunction "1_1") (pintype "passive"))
      (node (ref "R9") (pin "1") (pinfunction "1_1") (pintype "passive"))
    )
    (net (code "55") (name "Net-(IC2-VLIM)") (class "Default")
      (node (ref "IC2") (pin "19") (pinfunction "VLIM_19") (pintype "passive"))
      (node (ref "R10") (pin "1") (pinfunction "1_1") (pintype "passive"))
      (node (ref "R6") (pin "2") (pinfunction "2_2") (pintype "passive"))
    )
    (net (code "56") (name "Net-(IC2-~{CHGOK})") (class "Default")
      (node (ref "IC2") (pin "9") (pinfunction "~{CHGOK}_9") (pintype "passive"))
      (node (ref "R5") (pin "2") (pinfunction "2_2") (pintype "passive"))
    )
    (net (code "57") (name "Net-(IC4-FB)") (class "Default")
      (node (ref "IC4") (pin "7") (pinfunction "FB_7") (pintype "passive"))
      (node (ref "R20") (pin "2") (pinfunction "2_2") (pintype "passive"))
      (node (ref "R21") (pin "2") (pinfunction "2_2") (pintype "passive"))
    )
    (net (code "58") (name "Net-(IC4-SW)") (class "Default")
      (node (ref "I3") (pin "2") (pinfunction "2_2") (pintype "passive"))
      (node (ref "IC4") (pin "3") (pinfunction "SW_3") (pintype "passive"))
    )
    (net (code "59") (name "Net-(IC6-FB)") (class "Default")
      (node (ref "IC6") (pin "6") (pinfunction "FB_6") (pintype "passive"))
      (node (ref "R24") (pin "1") (pinfunction "1_1") (pintype "passive"))
      (node (ref "R26") (pin "2") (pinfunction "2_2") (pintype "passive"))
    )
    (net (code "60") (name "Net-(IC6-SW1)") (class "Default")
      (node (ref "I5") (pin "2") (pinfunction "2_2") (pintype "passive"))
      (node (ref "IC6") (pin "10") (pinfunction "SW1_10") (pintype "passive"))
    )
    (net (code "61") (name "Net-(IC6-SW2)") (class "Default")
      (node (ref "I5") (pin "1") (pinfunction "1_1") (pintype "passive"))
      (node (ref "IC6") (pin "8") (pinfunction "SW2_8") (pintype "passive"))
    )
    (net (code "62") (name "Net-(IC6-VCC)") (class "Default")
      (node (ref "C34") (pin "1") (pinfunction "1_1") (pintype "passive"))
      (node (ref "IC6") (pin "4") (pinfunction "VCC_4") (pintype "passive"))
    )
    (net (code "63") (name "Net-(IC7-REGOUT)") (class "Default")
      (node (ref "C50") (pin "1") (pinfunction "1_1") (pintype "passive"))
      (node (ref "IC7") (pin "10") (pinfunction "REGOUT_10") (pintype "passive"))
    )
    (net (code "64") (name "Net-(L1-K)") (class "Default")
      (node (ref "L1") (pin "1") (pinfunction "K_1") (pintype "passive"))
      (node (ref "R5") (pin "1") (pinfunction "1_1") (pintype "passive"))
    )
    (net (code "65") (name "Net-(L2-K)") (class "Default")
      (node (ref "L2") (pin "1") (pinfunction "K_1") (pintype "passive"))
      (node (ref "R7") (pin "1") (pinfunction "1_1") (pintype "passive"))
    )
    (net (code "66") (name "Net-(L3-K)") (class "Default")
      (node (ref "L3") (pin "1") (pinfunction "K_1") (pintype "passive"))
      (node (ref "R25") (pin "2") (pinfunction "2_2") (pintype "passive"))
    )
    (net (code "67") (name "Net-(L15-A)") (class "Default")
      (node (ref "L15") (pin "2") (pinfunction "A_2") (pintype "passive"))
      (node (ref "R102") (pin "2") (pinfunction "2_2") (pintype "passive"))
    )
    (net (code "68") (name "Net-(L15-K)") (class "Default")
      (node (ref "L15") (pin "1") (pinfunction "K_1") (pintype "passive"))
      (node (ref "Q1") (pin "3") (pinfunction "D_3") (pintype "passive"))
    )
    (net (code "69") (name "Net-(Q1-G)") (class "Default")
      (node (ref "Q1") (pin "1") (pinfunction "G_1") (pintype "passive"))
      (node (ref "R108") (pin "2") (pinfunction "2_2") (pintype "passive"))
    )
    (net (code "70") (name "Net-(U1-~{RTS})") (class "Default")
      (node (ref "C11") (pin "2") (pinfunction "2_2") (pintype "passive"))
      (node (ref "U1") (pin "4") (pinfunction "~{RTS}_4") (pintype "passive"))
    )
    (net (code "71") (name "Net-(U2-I1)") (class "Default")
      (node (ref "R57") (pin "2") (pinfunction "2_2") (pintype "passive"))
      (node (ref "R58") (pin "2") (pinfunction "2_2") (pintype "passive"))
      (node (ref "U2") (pin "1") (pinfunction "I1_1") (pintype "passive"))
      (node (ref "U2") (pin "2") (pinfunction "I2_2") (pintype "passive"))
    )
    (net (code "72") (name "Net-(U2-I3)") (class "Default")
      (node (ref "R59") (pin "2") (pinfunction "2_2") (pintype "passive"))
      (node (ref "R60") (pin "2") (pinfunction "2_2") (pintype "passive"))
      (node (ref "U2") (pin "3") (pinfunction "I3_3") (pintype "passive"))
      (node (ref "U2") (pin "4") (pinfunction "I4_4") (pintype "passive"))
    )
    (net (code "73") (name "Net-(U2-I5)") (class "Default")
      (node (ref "R61") (pin "2") (pinfunction "2_2") (pintype "passive"))
      (node (ref "R62") (pin "2") (pinfunction "2_2") (pintype "passive"))
      (node (ref "U2") (pin "5") (pinfunction "I5_5") (pintype "passive"))
      (node (ref "U2") (pin "6") (pinfunction "I6_6") (pintype "passive"))
    )
    (net (code "74") (name "Net-(U2-I7)") (class "Default")
      (node (ref "R63") (pin "2") (pinfunction "2_2") (pintype "passive"))
      (node (ref "R64") (pin "2") (pinfunction "2_2") (pintype "passive"))
      (node (ref "U2") (pin "7") (pinfunction "I7_7") (pintype "passive"))
      (node (ref "U2") (pin "8") (pinfunction "I8_8") (pintype "passive"))
    )
    (net (code "75") (name "Net-(W1-DI)") (class "Default")
      (node (ref "R2") (pin "1") (pinfunction "1_1") (pintype "passive"))
      (node (ref "S1") (pin "2") (pinfunction "2_2") (pintype "passive"))
      (node (ref "W1") (pin "3") (pinfunction "DI_3") (pintype "passive"))
    )
    (net (code "76") (name "VCC") (class "Default")
      (node (ref "B8") (pin "2") (pinfunction "2_2") (pintype "passive"))
      (node (ref "C35") (pin "1") (pinfunction "1_1") (pintype "passive"))
    )
    (net (code "77") (name "unconnected-(I1-ID-Pad4)") (class "Default")
      (node (ref "I1") (pin "4") (pinfunction "ID_4") (pintype "passive"))
    )
    (net (code "78") (name "unconnected-(IC1-I36-Pad4)") (class "Default")
      (node (ref "IC1") (pin "4") (pinfunction "I36_4") (pintype "passive"))
    )
    (net (code "79") (name "unconnected-(IC1-I37-Pad5)") (class "Default")
      (node (ref "IC1") (pin "5") (pinfunction "I37_5") (pintype "passive"))
    )
    (net (code "80") (name "unconnected-(IC1-I38-Pad6)") (class "Default")
      (node (ref "IC1") (pin "6") (pinfunction "I38_6") (pintype "passive"))
    )
    (net (code "81") (name "unconnected-(IC1-I39-Pad7)") (class "Default")
      (node (ref "IC1") (pin "7") (pinfunction "I39_7") (pintype "passive"))
    )
    (net (code "82") (name "unconnected-(IC1-IO9-Pad25)") (class "Default")
      (node (ref "IC1") (pin "25") (pinfunction "IO9_25") (pintype "passive"))
    )
    (net (code "83") (name "unconnected-(IC1-IO10-Pad26)") (class "Default")
      (node (ref "IC1") (pin "26") (pinfunction "IO10_26") (pintype "passive"))
    )
    (net (code "84") (name "unconnected-(IC1-NC_1-Pad23)") (class "Default")
      (node (ref "IC1") (pin "23") (pinfunction "NC_1_23") (pintype "passive"))
    )
    (net (code "85") (name "unconnected-(IC1-NC_2-Pad24)") (class "Default")
      (node (ref "IC1") (pin "24") (pinfunction "NC_2_24") (pintype "passive"))
    )
    (net (code "86") (name "unconnected-(IC1-NC_3-Pad28)") (class "Default")
      (node (ref "IC1") (pin "28") (pinfunction "NC_3_28") (pintype "passive"))
    )
    (net (code "87") (name "unconnected-(IC1-NC_4-Pad37)") (class "Default")
      (node (ref "IC1") (pin "37") (pinfunction "NC_4_37") (pintype "passive"))
    )
    (net (code "88") (name "unconnected-(IC4-NC-Pad5)") (class "Default")
      (node (ref "IC4") (pin "5") (pinfunction "NC_5") (pintype "passive"))
    )
    (net (code "89") (name "unconnected-(IC6-PG-Pad3)") (class "Default")
      (node (ref "IC6") (pin "3") (pinfunction "PG_3") (pintype "passive"))
    )
    (net (code "90") (name "unconnected-(IC7-AUX_CL-Pad7)") (class "Default")
      (node (ref "IC7") (pin "7") (pinfunction "AUX_CL_7") (pintype "passive"))
    )
    (net (code "91") (name "unconnected-(IC7-AUX_DA-Pad21)") (class "Default")
      (node (ref "IC7") (pin "21") (pinfunction "AUX_DA_21") (pintype "passive"))
    )
    (net (code "92") (name "unconnected-(IC7-INT-Pad12)") (class "Default")
      (node (ref "IC7") (pin "12") (pinfunction "INT_12") (pintype "passive"))
    )
    (net (code "93") (name "unconnected-(IC7-NC_1-Pad2)") (class "Default")
      (node (ref "IC7") (pin "2") (pinfunction "NC_1_2") (pintype "passive"))
    )
    (net (code "94") (name "unconnected-(IC7-NC_2-Pad3)") (class "Default")
      (node (ref "IC7") (pin "3") (pinfunction "NC_2_3") (pintype "passive"))
    )
    (net (code "95") (name "unconnected-(IC7-NC_3-Pad4)") (class "Default")
      (node (ref "IC7") (pin "4") (pinfunction "NC_3_4") (pintype "passive"))
    )
    (net (code "96") (name "unconnected-(IC7-NC_4-Pad5)") (class "Default")
      (node (ref "IC7") (pin "5") (pinfunction "NC_4_5") (pintype "passive"))
    )
    (net (code "97") (name "unconnected-(IC7-NC_5-Pad6)") (class "Default")
      (node (ref "IC7") (pin "6") (pinfunction "NC_5_6") (pintype "passive"))
    )
    (net (code "98") (name "unconnected-(IC7-NC_6-Pad14)") (class "Default")
      (node (ref "IC7") (pin "14") (pinfunction "NC_6_14") (pintype "passive"))
    )
    (net (code "99") (name "unconnected-(IC7-NC_7-Pad15)") (class "Default")
      (node (ref "IC7") (pin "15") (pinfunction "NC_7_15") (pintype "passive"))
    )
    (net (code "100") (name "unconnected-(IC7-NC_8-Pad16)") (class "Default")
      (node (ref "IC7") (pin "16") (pinfunction "NC_8_16") (pintype "passive"))
    )
    (net (code "101") (name "unconnected-(IC7-NC_9-Pad17)") (class "Default")
      (node (ref "IC7") (pin "17") (pinfunction "NC_9_17") (pintype "passive"))
    )
    (net (code "102") (name "unconnected-(IC7-RESV_NC-Pad19)") (class "Default")
      (node (ref "IC7") (pin "19") (pinfunction "RESV_NC_19") (pintype "passive"))
    )
    (net (code "103") (name "unconnected-(M1-Pad3)") (class "Default")
      (node (ref "M1") (pin "3") (pinfunction "3_3") (pintype "passive"))
    )
    (net (code "104") (name "unconnected-(M1-Pad6)") (class "Default")
      (node (ref "M1") (pin "6") (pinfunction "6_6") (pintype "passive"))
    )
    (net (code "105") (name "unconnected-(MS2-NC-Pad1)") (class "Default")
      (node (ref "MS2") (pin "1") (pinfunction "NC_1") (pintype "passive"))
    )
    (net (code "106") (name "unconnected-(MS2-NC-Pad8)") (class "Default")
      (node (ref "MS2") (pin "8") (pinfunction "NC_8") (pintype "passive"))
    )
    (net (code "107") (name "unconnected-(U1-TWON{slash}DTR-Pad6)") (class "Default")
      (node (ref "U1") (pin "6") (pinfunction "TWON/DTR_6") (pintype "passive"))
    )
    (net (code "108") (name "unconnected-(U1-~{CTS}-Pad5)") (class "Default")
      (node (ref "U1") (pin "5") (pinfunction "~{CTS}_5") (pintype "passive"))
    )
    (net (code "109") (name "unconnected-(U12-NC-Pad4)") (class "Default")
      (node (ref "U12") (pin "4") (pinfunction "NC_4") (pintype "passive"))
    )
    (net (code "110") (name "unconnected-(U12-~{OUT}-Pad3)") (class "Default")
      (node (ref "U12") (pin "3") (pinfunction "~{OUT}_3") (pintype "passive"))
    )
    (net (code "111") (name "unconnected-(W1-DO-Pad1)") (class "Default")
      (node (ref "W1") (pin "1") (pinfunction "DO_1") (pintype "passive"))
    )
  )
)
